# 04_CONNECTOR_OUT.net
KiCad netlist of a schematic drawn in Altium Designer
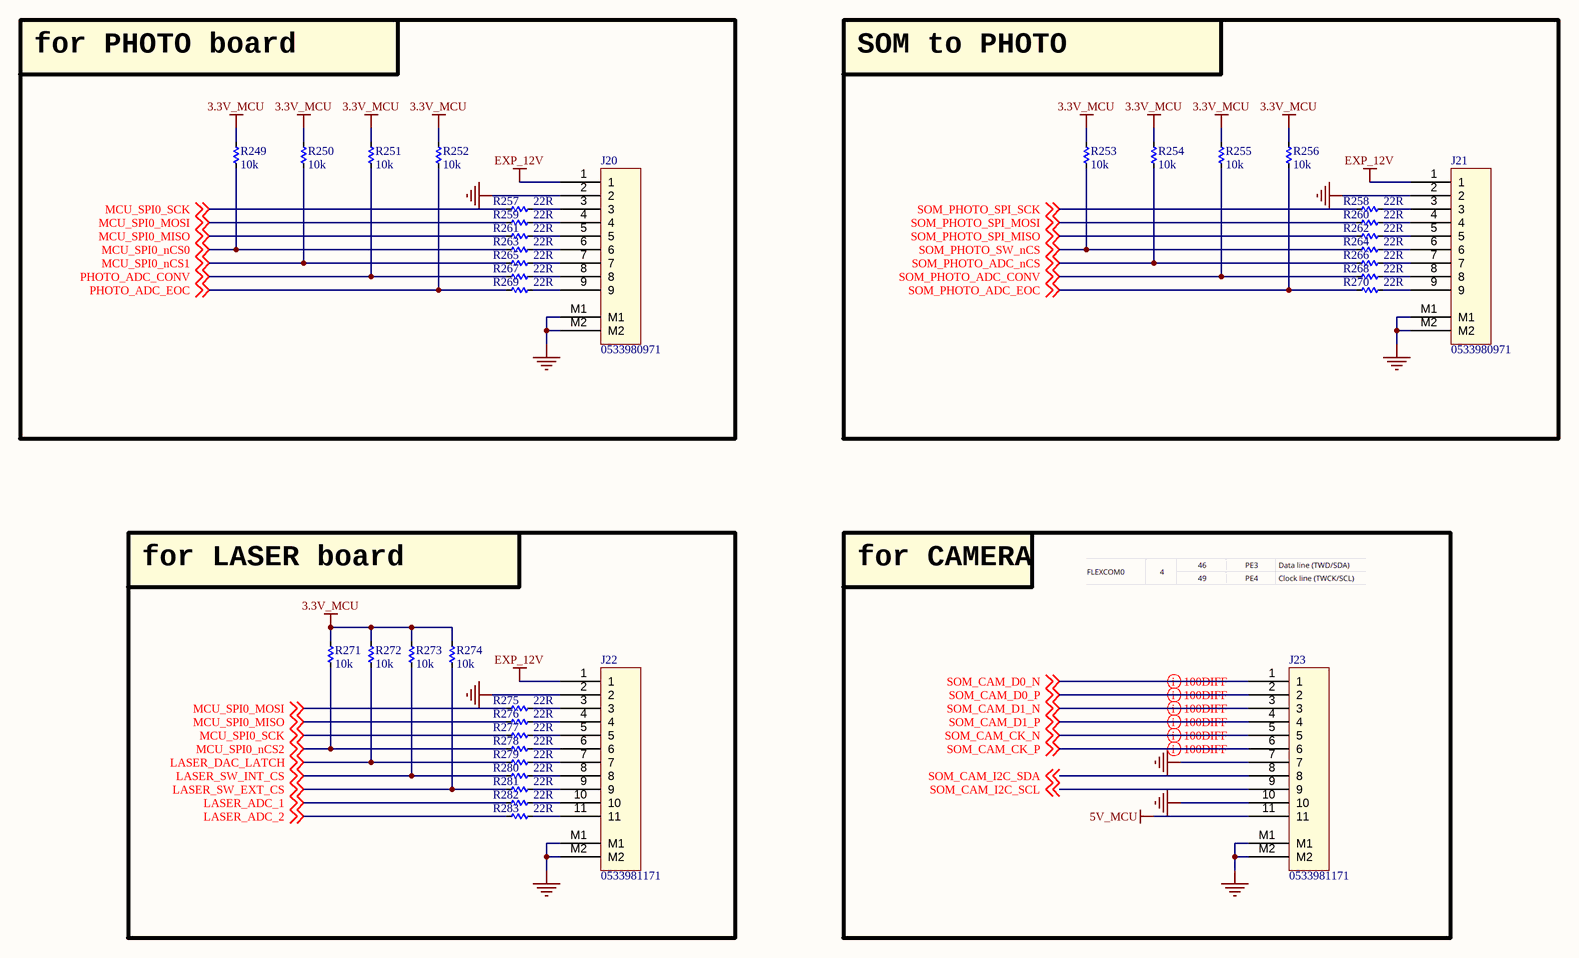
[diagram p0: 04_CONNECTOR_OUT.SchDoc]

(export (version "E")
  (design (tool "Eeschema 10.0.6"))
  (components
    (comp (ref "J20")
      (value "0533980971")
      (footprint "MOLEX_0533980971")
      (libsource (lib "LABLIB") (part "Header 9x1_2M"))
    )
    (comp (ref "J21")
      (value "0533980971")
      (footprint "MOLEX_0533980971")
      (libsource (lib "LABLIB") (part "Header 9x1_2M"))
    )
    (comp (ref "J22")
      (value "0533981171")
      (footprint "MOLEX_0533981171")
      (libsource (lib "LABLIB") (part "Header 11x1_2M"))
    )
    (comp (ref "J23") (value "0533981171") (libsource (lib "LABLIB") (part "Header 11x1_2M")))
    (comp (ref "R249")
      (value "10k")
      (footprint "RES_C_1005X40")
      (description "RES")
      (libsource (lib "LABLIB") (part "_RES_B_2"))
    )
    (comp (ref "R250")
      (value "10k")
      (footprint "RES_C_1005X40")
      (description "RES")
      (libsource (lib "LABLIB") (part "_RES_B_2"))
    )
    (comp (ref "R251")
      (value "10k")
      (footprint "RES_C_1005X40")
      (description "RES")
      (libsource (lib "LABLIB") (part "_RES_B_2"))
    )
    (comp (ref "R252")
      (value "10k")
      (footprint "RES_C_1005X40")
      (description "RES")
      (libsource (lib "LABLIB") (part "_RES_B_2"))
    )
    (comp (ref "R253")
      (value "10k")
      (footprint "RES_C_1005X40")
      (description "RES")
      (libsource (lib "LABLIB") (part "_RES_B_2"))
    )
    (comp (ref "R254")
      (value "10k")
      (footprint "RES_C_1005X40")
      (description "RES")
      (libsource (lib "LABLIB") (part "_RES_B_2"))
    )
    (comp (ref "R255")
      (value "10k")
      (footprint "RES_C_1005X40")
      (description "RES")
      (libsource (lib "LABLIB") (part "_RES_B_2"))
    )
    (comp (ref "R256")
      (value "10k")
      (footprint "RES_C_1005X40")
      (description "RES")
      (libsource (lib "LABLIB") (part "_RES_B_2"))
    )
    (comp (ref "R257")
      (value "22R")
      (footprint "RES_C_1005X40")
      (description "RES")
      (libsource (lib "LABLIB") (part "_RES_B_2"))
    )
    (comp (ref "R258")
      (value "22R")
      (footprint "RES_C_1005X40")
      (description "RES")
      (libsource (lib "LABLIB") (part "_RES_B_2"))
    )
    (comp (ref "R259")
      (value "22R")
      (footprint "RES_C_1005X40")
      (description "RES")
      (libsource (lib "LABLIB") (part "_RES_B_2"))
    )
    (comp (ref "R260")
      (value "22R")
      (footprint "RES_C_1005X40")
      (description "RES")
      (libsource (lib "LABLIB") (part "_RES_B_2"))
    )
    (comp (ref "R261")
      (value "22R")
      (footprint "RES_C_1005X40")
      (description "RES")
      (libsource (lib "LABLIB") (part "_RES_B_2"))
    )
    (comp (ref "R262")
      (value "22R")
      (footprint "RES_C_1005X40")
      (description "RES")
      (libsource (lib "LABLIB") (part "_RES_B_2"))
    )
    (comp (ref "R263")
      (value "22R")
      (footprint "RES_C_1005X40")
      (description "RES")
      (libsource (lib "LABLIB") (part "_RES_B_2"))
    )
    (comp (ref "R264")
      (value "22R")
      (footprint "RES_C_1005X40")
      (description "RES")
      (libsource (lib "LABLIB") (part "_RES_B_2"))
    )
    (comp (ref "R265")
      (value "22R")
      (footprint "RES_C_1005X40")
      (description "RES")
      (libsource (lib "LABLIB") (part "_RES_B_2"))
    )
    (comp (ref "R266")
      (value "22R")
      (footprint "RES_C_1005X40")
      (description "RES")
      (libsource (lib "LABLIB") (part "_RES_B_2"))
    )
    (comp (ref "R267")
      (value "22R")
      (footprint "RES_C_1005X40")
      (description "RES")
      (libsource (lib "LABLIB") (part "_RES_B_2"))
    )
    (comp (ref "R268")
      (value "22R")
      (footprint "RES_C_1005X40")
      (description "RES")
      (libsource (lib "LABLIB") (part "_RES_B_2"))
    )
    (comp (ref "R269")
      (value "22R")
      (footprint "RES_C_1005X40")
      (description "RES")
      (libsource (lib "LABLIB") (part "_RES_B_2"))
    )
    (comp (ref "R270")
      (value "22R")
      (footprint "RES_C_1005X40")
      (description "RES")
      (libsource (lib "LABLIB") (part "_RES_B_2"))
    )
    (comp (ref "R271")
      (value "10k")
      (footprint "RES_C_1005X40")
      (description "RES")
      (libsource (lib "LABLIB") (part "_RES_B_2"))
    )
    (comp (ref "R272")
      (value "10k")
      (footprint "RES_C_1005X40")
      (description "RES")
      (libsource (lib "LABLIB") (part "_RES_B_2"))
    )
    (comp (ref "R273")
      (value "10k")
      (footprint "RES_C_1005X40")
      (description "RES")
      (libsource (lib "LABLIB") (part "_RES_B_2"))
    )
    (comp (ref "R274")
      (value "10k")
      (footprint "RES_C_1005X40")
      (description "RES")
      (libsource (lib "LABLIB") (part "_RES_B_2"))
    )
    (comp (ref "R275")
      (value "22R")
      (footprint "RES_C_1005X40")
      (description "RES")
      (libsource (lib "LABLIB") (part "_RES_B_2"))
    )
    (comp (ref "R276")
      (value "22R")
      (footprint "RES_C_1005X40")
      (description "RES")
      (libsource (lib "LABLIB") (part "_RES_B_2"))
    )
    (comp (ref "R277")
      (value "22R")
      (footprint "RES_C_1005X40")
      (description "RES")
      (libsource (lib "LABLIB") (part "_RES_B_2"))
    )
    (comp (ref "R278")
      (value "22R")
      (footprint "RES_C_1005X40")
      (description "RES")
      (libsource (lib "LABLIB") (part "_RES_B_2"))
    )
    (comp (ref "R279")
      (value "22R")
      (footprint "RES_C_1005X40")
      (description "RES")
      (libsource (lib "LABLIB") (part "_RES_B_2"))
    )
    (comp (ref "R280")
      (value "22R")
      (footprint "RES_C_1005X40")
      (description "RES")
      (libsource (lib "LABLIB") (part "_RES_B_2"))
    )
    (comp (ref "R281")
      (value "22R")
      (footprint "RES_C_1005X40")
      (description "RES")
      (libsource (lib "LABLIB") (part "_RES_B_2"))
    )
    (comp (ref "R282")
      (value "22R")
      (footprint "RES_C_1005X40")
      (description "RES")
      (libsource (lib "LABLIB") (part "_RES_B_2"))
    )
    (comp (ref "R283")
      (value "22R")
      (footprint "RES_C_1005X40")
      (description "RES")
      (libsource (lib "LABLIB") (part "_RES_B_2"))
    )
  )
  (nets
    (net (code "1") (name "3.3V_MCU") (class "Default")
      (node (ref "R249") (pin "1") (pinfunction "1_1") (pintype "passive"))
      (node (ref "R250") (pin "1") (pinfunction "1_1") (pintype "passive"))
      (node (ref "R251") (pin "1") (pinfunction "1_1") (pintype "passive"))
      (node (ref "R252") (pin "1") (pinfunction "1_1") (pintype "passive"))
      (node (ref "R253") (pin "1") (pinfunction "1_1") (pintype "passive"))
      (node (ref "R254") (pin "1") (pinfunction "1_1") (pintype "passive"))
      (node (ref "R255") (pin "1") (pinfunction "1_1") (pintype "passive"))
      (node (ref "R256") (pin "1") (pinfunction "1_1") (pintype "passive"))
      (node (ref "R271") (pin "1") (pinfunction "1_1") (pintype "passive"))
      (node (ref "R272") (pin "1") (pinfunction "1_1") (pintype "passive"))
      (node (ref "R273") (pin "1") (pinfunction "1_1") (pintype "passive"))
      (node (ref "R274") (pin "1") (pinfunction "1_1") (pintype "passive"))
    )
    (net (code "2") (name "5V_MCU") (class "Default")
      (node (ref "J23") (pin "11") (pinfunction "11_11") (pintype "passive"))
    )
    (net (code "3") (name "EXP_12V") (class "Default")
      (node (ref "J20") (pin "1") (pinfunction "1_1") (pintype "passive"))
      (node (ref "J21") (pin "1") (pinfunction "1_1") (pintype "passive"))
      (node (ref "J22") (pin "1") (pinfunction "1_1") (pintype "passive"))
    )
    (net (code "4") (name "GND") (class "Default")
      (node (ref "J20") (pin "2") (pinfunction "2_2") (pintype "passive"))
      (node (ref "J20") (pin "M1") (pinfunction "M1_M1") (pintype "passive"))
      (node (ref "J20") (pin "M2") (pinfunction "M2_M2") (pintype "passive"))
      (node (ref "J21") (pin "2") (pinfunction "2_2") (pintype "passive"))
      (node (ref "J21") (pin "M1") (pinfunction "M1_M1") (pintype "passive"))
      (node (ref "J21") (pin "M2") (pinfunction "M2_M2") (pintype "passive"))
      (node (ref "J22") (pin "2") (pinfunction "2_2") (pintype "passive"))
      (node (ref "J22") (pin "M1") (pinfunction "M1_M1") (pintype "passive"))
      (node (ref "J22") (pin "M2") (pinfunction "M2_M2") (pintype "passive"))
      (node (ref "J23") (pin "10") (pinfunction "10_10") (pintype "passive"))
      (node (ref "J23") (pin "7") (pinfunction "7_7") (pintype "passive"))
      (node (ref "J23") (pin "M1") (pinfunction "M1_M1") (pintype "passive"))
      (node (ref "J23") (pin "M2") (pinfunction "M2_M2") (pintype "passive"))
    )
    (net (code "5") (name "LASER_ADC_1") (class "Default")
      (node (ref "R282") (pin "1") (pinfunction "1_1") (pintype "passive"))
    )
    (net (code "6") (name "LASER_ADC_2") (class "Default")
      (node (ref "R283") (pin "1") (pinfunction "1_1") (pintype "passive"))
    )
    (net (code "7") (name "LASER_DAC_LATCH") (class "Default")
      (node (ref "R272") (pin "2") (pinfunction "2_2") (pintype "passive"))
      (node (ref "R279") (pin "1") (pinfunction "1_1") (pintype "passive"))
    )
    (net (code "8") (name "LASER_SW_EXT_CS") (class "Default")
      (node (ref "R274") (pin "2") (pinfunction "2_2") (pintype "passive"))
      (node (ref "R281") (pin "1") (pinfunction "1_1") (pintype "passive"))
    )
    (net (code "9") (name "LASER_SW_INT_CS") (class "Default")
      (node (ref "R273") (pin "2") (pinfunction "2_2") (pintype "passive"))
      (node (ref "R280") (pin "1") (pinfunction "1_1") (pintype "passive"))
    )
    (net (code "10") (name "MCU_SPI0_MISO") (class "Default")
      (node (ref "R261") (pin "1") (pinfunction "1_1") (pintype "passive"))
      (node (ref "R276") (pin "1") (pinfunction "1_1") (pintype "passive"))
    )
    (net (code "11") (name "MCU_SPI0_MOSI") (class "Default")
      (node (ref "R259") (pin "1") (pinfunction "1_1") (pintype "passive"))
      (node (ref "R275") (pin "1") (pinfunction "1_1") (pintype "passive"))
    )
    (net (code "12") (name "MCU_SPI0_SCK") (class "Default")
      (node (ref "R257") (pin "1") (pinfunction "1_1") (pintype "passive"))
      (node (ref "R277") (pin "1") (pinfunction "1_1") (pintype "passive"))
    )
    (net (code "13") (name "MCU_SPI0_nCS0") (class "Default")
      (node (ref "R249") (pin "2") (pinfunction "2_2") (pintype "passive"))
      (node (ref "R263") (pin "1") (pinfunction "1_1") (pintype "passive"))
    )
    (net (code "14") (name "MCU_SPI0_nCS1") (class "Default")
      (node (ref "R250") (pin "2") (pinfunction "2_2") (pintype "passive"))
      (node (ref "R265") (pin "1") (pinfunction "1_1") (pintype "passive"))
    )
    (net (code "15") (name "MCU_SPI0_nCS2") (class "Default")
      (node (ref "R271") (pin "2") (pinfunction "2_2") (pintype "passive"))
      (node (ref "R278") (pin "1") (pinfunction "1_1") (pintype "passive"))
    )
    (net (code "16") (name "Net-(J20-Pad3)") (class "Default")
      (node (ref "J20") (pin "3") (pinfunction "3_3") (pintype "passive"))
      (node (ref "R257") (pin "2") (pinfunction "2_2") (pintype "passive"))
    )
    (net (code "17") (name "Net-(J20-Pad4)") (class "Default")
      (node (ref "J20") (pin "4") (pinfunction "4_4") (pintype "passive"))
      (node (ref "R259") (pin "2") (pinfunction "2_2") (pintype "passive"))
    )
    (net (code "18") (name "Net-(J20-Pad5)") (class "Default")
      (node (ref "J20") (pin "5") (pinfunction "5_5") (pintype "passive"))
      (node (ref "R261") (pin "2") (pinfunction "2_2") (pintype "passive"))
    )
    (net (code "19") (name "Net-(J20-Pad6)") (class "Default")
      (node (ref "J20") (pin "6") (pinfunction "6_6") (pintype "passive"))
      (node (ref "R263") (pin "2") (pinfunction "2_2") (pintype "passive"))
    )
    (net (code "20") (name "Net-(J20-Pad7)") (class "Default")
      (node (ref "J20") (pin "7") (pinfunction "7_7") (pintype "passive"))
      (node (ref "R265") (pin "2") (pinfunction "2_2") (pintype "passive"))
    )
    (net (code "21") (name "Net-(J20-Pad8)") (class "Default")
      (node (ref "J20") (pin "8") (pinfunction "8_8") (pintype "passive"))
      (node (ref "R267") (pin "2") (pinfunction "2_2") (pintype "passive"))
    )
    (net (code "22") (name "Net-(J20-Pad9)") (class "Default")
      (node (ref "J20") (pin "9") (pinfunction "9_9") (pintype "passive"))
      (node (ref "R269") (pin "2") (pinfunction "2_2") (pintype "passive"))
    )
    (net (code "23") (name "Net-(J21-Pad3)") (class "Default")
      (node (ref "J21") (pin "3") (pinfunction "3_3") (pintype "passive"))
      (node (ref "R258") (pin "2") (pinfunction "2_2") (pintype "passive"))
    )
    (net (code "24") (name "Net-(J21-Pad4)") (class "Default")
      (node (ref "J21") (pin "4") (pinfunction "4_4") (pintype "passive"))
      (node (ref "R260") (pin "2") (pinfunction "2_2") (pintype "passive"))
    )
    (net (code "25") (name "Net-(J21-Pad5)") (class "Default")
      (node (ref "J21") (pin "5") (pinfunction "5_5") (pintype "passive"))
      (node (ref "R262") (pin "2") (pinfunction "2_2") (pintype "passive"))
    )
    (net (code "26") (name "Net-(J21-Pad6)") (class "Default")
      (node (ref "J21") (pin "6") (pinfunction "6_6") (pintype "passive"))
      (node (ref "R264") (pin "2") (pinfunction "2_2") (pintype "passive"))
    )
    (net (code "27") (name "Net-(J21-Pad7)") (class "Default")
      (node (ref "J21") (pin "7") (pinfunction "7_7") (pintype "passive"))
      (node (ref "R266") (pin "2") (pinfunction "2_2") (pintype "passive"))
    )
    (net (code "28") (name "Net-(J21-Pad8)") (class "Default")
      (node (ref "J21") (pin "8") (pinfunction "8_8") (pintype "passive"))
      (node (ref "R268") (pin "2") (pinfunction "2_2") (pintype "passive"))
    )
    (net (code "29") (name "Net-(J21-Pad9)") (class "Default")
      (node (ref "J21") (pin "9") (pinfunction "9_9") (pintype "passive"))
      (node (ref "R270") (pin "2") (pinfunction "2_2") (pintype "passive"))
    )
    (net (code "30") (name "Net-(J22-Pad3)") (class "Default")
      (node (ref "J22") (pin "3") (pinfunction "3_3") (pintype "passive"))
      (node (ref "R275") (pin "2") (pinfunction "2_2") (pintype "passive"))
    )
    (net (code "31") (name "Net-(J22-Pad4)") (class "Default")
      (node (ref "J22") (pin "4") (pinfunction "4_4") (pintype "passive"))
      (node (ref "R276") (pin "2") (pinfunction "2_2") (pintype "passive"))
    )
    (net (code "32") (name "Net-(J22-Pad5)") (class "Default")
      (node (ref "J22") (pin "5") (pinfunction "5_5") (pintype "passive"))
      (node (ref "R277") (pin "2") (pinfunction "2_2") (pintype "passive"))
    )
    (net (code "33") (name "Net-(J22-Pad6)") (class "Default")
      (node (ref "J22") (pin "6") (pinfunction "6_6") (pintype "passive"))
      (node (ref "R278") (pin "2") (pinfunction "2_2") (pintype "passive"))
    )
    (net (code "34") (name "Net-(J22-Pad7)") (class "Default")
      (node (ref "J22") (pin "7") (pinfunction "7_7") (pintype "passive"))
      (node (ref "R279") (pin "2") (pinfunction "2_2") (pintype "passive"))
    )
    (net (code "35") (name "Net-(J22-Pad8)") (class "Default")
      (node (ref "J22") (pin "8") (pinfunction "8_8") (pintype "passive"))
      (node (ref "R280") (pin "2") (pinfunction "2_2") (pintype "passive"))
    )
    (net (code "36") (name "Net-(J22-Pad9)") (class "Default")
      (node (ref "J22") (pin "9") (pinfunction "9_9") (pintype "passive"))
      (node (ref "R281") (pin "2") (pinfunction "2_2") (pintype "passive"))
    )
    (net (code "37") (name "Net-(J22-Pad10)") (class "Default")
      (node (ref "J22") (pin "10") (pinfunction "10_10") (pintype "passive"))
      (node (ref "R282") (pin "2") (pinfunction "2_2") (pintype "passive"))
    )
    (net (code "38") (name "Net-(J22-Pad11)") (class "Default")
      (node (ref "J22") (pin "11") (pinfunction "11_11") (pintype "passive"))
      (node (ref "R283") (pin "2") (pinfunction "2_2") (pintype "passive"))
    )
    (net (code "39") (name "PHOTO_ADC_CONV") (class "Default")
      (node (ref "R251") (pin "2") (pinfunction "2_2") (pintype "passive"))
      (node (ref "R267") (pin "1") (pinfunction "1_1") (pintype "passive"))
    )
    (net (code "40") (name "PHOTO_ADC_EOC") (class "Default")
      (node (ref "R252") (pin "2") (pinfunction "2_2") (pintype "passive"))
      (node (ref "R269") (pin "1") (pinfunction "1_1") (pintype "passive"))
    )
    (net (code "41") (name "SOM_CAM_CK_N") (class "Default")
      (node (ref "J23") (pin "5") (pinfunction "5_5") (pintype "passive"))
    )
    (net (code "42") (name "SOM_CAM_CK_P") (class "Default")
      (node (ref "J23") (pin "6") (pinfunction "6_6") (pintype "passive"))
    )
    (net (code "43") (name "SOM_CAM_D0_N") (class "Default")
      (node (ref "J23") (pin "1") (pinfunction "1_1") (pintype "passive"))
    )
    (net (code "44") (name "SOM_CAM_D0_P") (class "Default")
      (node (ref "J23") (pin "2") (pinfunction "2_2") (pintype "passive"))
    )
    (net (code "45") (name "SOM_CAM_D1_N") (class "Default")
      (node (ref "J23") (pin "3") (pinfunction "3_3") (pintype "passive"))
    )
    (net (code "46") (name "SOM_CAM_D1_P") (class "Default")
      (node (ref "J23") (pin "4") (pinfunction "4_4") (pintype "passive"))
    )
    (net (code "47") (name "SOM_CAM_I2C_SCL") (class "Default")
      (node (ref "J23") (pin "9") (pinfunction "9_9") (pintype "passive"))
    )
    (net (code "48") (name "SOM_CAM_I2C_SDA") (class "Default")
      (node (ref "J23") (pin "8") (pinfunction "8_8") (pintype "passive"))
    )
    (net (code "49") (name "SOM_PHOTO_ADC_CONV") (class "Default")
      (node (ref "R255") (pin "2") (pinfunction "2_2") (pintype "passive"))
      (node (ref "R268") (pin "1") (pinfunction "1_1") (pintype "passive"))
    )
    (net (code "50") (name "SOM_PHOTO_ADC_EOC") (class "Default")
      (node (ref "R256") (pin "2") (pinfunction "2_2") (pintype "passive"))
      (node (ref "R270") (pin "1") (pinfunction "1_1") (pintype "passive"))
    )
    (net (code "51") (name "SOM_PHOTO_ADC_nCS") (class "Default")
      (node (ref "R254") (pin "2") (pinfunction "2_2") (pintype "passive"))
      (node (ref "R266") (pin "1") (pinfunction "1_1") (pintype "passive"))
    )
    (net (code "52") (name "SOM_PHOTO_SPI_MISO") (class "Default")
      (node (ref "R262") (pin "1") (pinfunction "1_1") (pintype "passive"))
    )
    (net (code "53") (name "SOM_PHOTO_SPI_MOSI") (class "Default")
      (node (ref "R260") (pin "1") (pinfunction "1_1") (pintype "passive"))
    )
    (net (code "54") (name "SOM_PHOTO_SPI_SCK") (class "Default")
      (node (ref "R258") (pin "1") (pinfunction "1_1") (pintype "passive"))
    )
    (net (code "55") (name "SOM_PHOTO_SW_nCS") (class "Default")
      (node (ref "R253") (pin "2") (pinfunction "2_2") (pintype "passive"))
      (node (ref "R264") (pin "1") (pinfunction "1_1") (pintype "passive"))
    )
  )
)
